# TestPCB2.net
KiCad netlist of a schematic drawn in Altium Designer
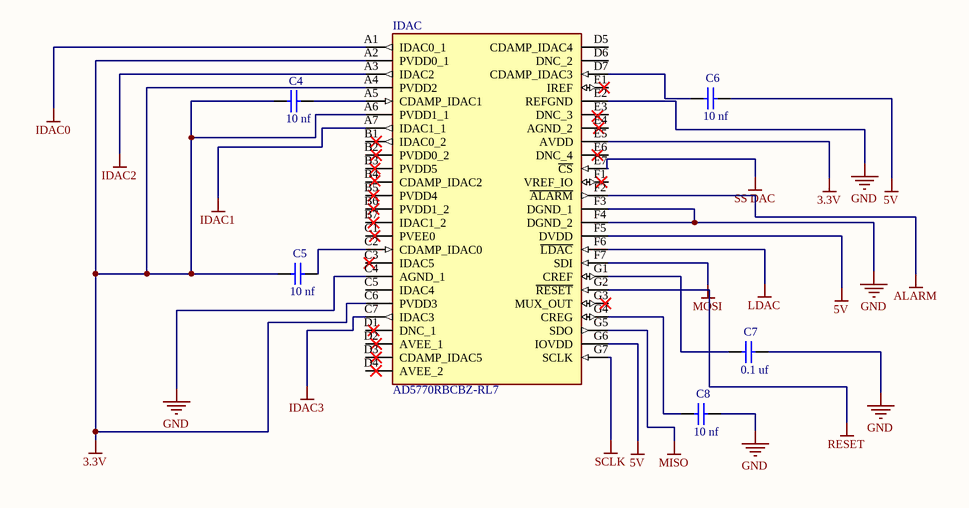
[diagram p0: TestPCB2.SchDoc]

(export (version "E")
  (design (tool "Eeschema 10.0.6"))
  (components
    (comp (ref "C4")
      (value "10 nf")
      (footprint "CAPC2013X94X50ML20T25")
      (fields
        (field (name "MANUFACTURER") "AVX Interconnect / Elco")
        (field (name "PART NUMBER") "08051C104JAT2A")
      )
      (libsource (lib "Altium Content Vault") (part "CAP"))
    )
    (comp (ref "C5")
      (value "10 nf")
      (footprint "CAPC2013X94X50ML20T25")
      (fields
        (field (name "MANUFACTURER") "AVX Interconnect / Elco")
        (field (name "PART NUMBER") "08051C104JAT2A")
      )
      (libsource (lib "Altium Content Vault") (part "CAP"))
    )
    (comp (ref "C6")
      (value "10 nf")
      (footprint "CAPC2013X94X50ML20T25")
      (fields
        (field (name "MANUFACTURER") "AVX Interconnect / Elco")
        (field (name "PART NUMBER") "08051C104JAT2A")
      )
      (libsource (lib "Altium Content Vault") (part "CAP"))
    )
    (comp (ref "C7")
      (value "0.1 uf")
      (footprint "CAPC2013X94X50ML20T25")
      (fields
        (field (name "MANUFACTURER") "AVX Interconnect / Elco")
        (field (name "PART NUMBER") "08051C104JAT2A")
      )
      (libsource (lib "Altium Content Vault") (part "CAP"))
    )
    (comp (ref "C8")
      (value "10 nf")
      (footprint "CAPC2013X94X50ML20T25")
      (fields
        (field (name "MANUFACTURER") "AVX Interconnect / Elco")
        (field (name "PART NUMBER") "08051C104JAT2A")
      )
      (libsource (lib "Altium Content Vault") (part "CAP"))
    )
    (comp (ref "IDAC")
      (value "AD5770RBCBZ-RL7")
      (footprint "SamacSys:BGA49C50P7X7_404X404X66")
      (description "Integrated Circuit")
      (fields (field (name "MOUSER PART NUMBER") "584-AD5770RBCBZ-RL7"))
      (libsource (lib "*") (part "AD5770RBCBZ-RL7"))
    )
  )
  (nets
    (net (code "1") (name "3.3V") (class "Default")
      (node (ref "C4") (pin "1") (pinfunction "1_1") (pintype "passive"))
      (node (ref "C5") (pin "1") (pinfunction "1_1") (pintype "passive"))
      (node (ref "IDAC") (pin "A2") (pinfunction "PVDD0_1_A2") (pintype "power_in"))
      (node (ref "IDAC") (pin "A4") (pinfunction "PVDD2_A4") (pintype "power_in"))
      (node (ref "IDAC") (pin "A6") (pinfunction "PVDD1_1_A6") (pintype "power_in"))
      (node (ref "IDAC") (pin "C6") (pinfunction "PVDD3_C6") (pintype "power_in"))
      (node (ref "IDAC") (pin "E5") (pinfunction "AVDD_E5") (pintype "power_in"))
    )
    (net (code "2") (name "5V") (class "Default")
      (node (ref "C6") (pin "2") (pinfunction "2_2") (pintype "passive"))
      (node (ref "IDAC") (pin "F5") (pinfunction "DVDD_F5") (pintype "power_in"))
      (node (ref "IDAC") (pin "G6") (pinfunction "IOVDD_G6") (pintype "power_in"))
    )
    (net (code "3") (name "ALARM") (class "Default")
      (node (ref "IDAC") (pin "F2") (pinfunction "~{ALARM}_F2") (pintype "output"))
    )
    (net (code "4") (name "GND") (class "Default")
      (node (ref "C7") (pin "2") (pinfunction "2_2") (pintype "passive"))
      (node (ref "C8") (pin "2") (pinfunction "2_2") (pintype "passive"))
      (node (ref "IDAC") (pin "C4") (pinfunction "AGND_1_C4") (pintype "power_in"))
      (node (ref "IDAC") (pin "E2") (pinfunction "REFGND_E2") (pintype "power_in"))
      (node (ref "IDAC") (pin "F3") (pinfunction "DGND_1_F3") (pintype "power_in"))
      (node (ref "IDAC") (pin "F4") (pinfunction "DGND_2_F4") (pintype "power_in"))
    )
    (net (code "5") (name "IDAC0") (class "Default")
      (node (ref "IDAC") (pin "A1") (pinfunction "IDAC0_1_A1") (pintype "output"))
    )
    (net (code "6") (name "IDAC1") (class "Default")
      (node (ref "IDAC") (pin "A7") (pinfunction "IDAC1_1_A7") (pintype "output"))
    )
    (net (code "7") (name "IDAC2") (class "Default")
      (node (ref "IDAC") (pin "A3") (pinfunction "IDAC2_A3") (pintype "output"))
    )
    (net (code "8") (name "IDAC3") (class "Default")
      (node (ref "IDAC") (pin "C7") (pinfunction "IDAC3_C7") (pintype "output"))
    )
    (net (code "9") (name "LDAC") (class "Default")
      (node (ref "IDAC") (pin "F6") (pinfunction "~{LDAC}_F6") (pintype "input"))
    )
    (net (code "10") (name "MISO") (class "Default")
      (node (ref "IDAC") (pin "G5") (pinfunction "SDO_G5") (pintype "output"))
    )
    (net (code "11") (name "MOSI") (class "Default")
      (node (ref "IDAC") (pin "F7") (pinfunction "SDI_F7") (pintype "input"))
    )
    (net (code "12") (name "Net-(IDAC-CDAMP_IDAC0)") (class "Default")
      (node (ref "C5") (pin "2") (pinfunction "2_2") (pintype "passive"))
      (node (ref "IDAC") (pin "C2") (pinfunction "CDAMP_IDAC0_C2") (pintype "input"))
    )
    (net (code "13") (name "Net-(IDAC-CDAMP_IDAC1)") (class "Default")
      (node (ref "C4") (pin "2") (pinfunction "2_2") (pintype "passive"))
      (node (ref "IDAC") (pin "A5") (pinfunction "CDAMP_IDAC1_A5") (pintype "input"))
    )
    (net (code "14") (name "Net-(IDAC-CDAMP_IDAC3)") (class "Default")
      (node (ref "C6") (pin "1") (pinfunction "1_1") (pintype "passive"))
      (node (ref "IDAC") (pin "D7") (pinfunction "CDAMP_IDAC3_D7") (pintype "input"))
    )
    (net (code "15") (name "Net-(IDAC-CREF)") (class "Default")
      (node (ref "C7") (pin "1") (pinfunction "1_1") (pintype "passive"))
      (node (ref "IDAC") (pin "G1") (pinfunction "CREF_G1") (pintype "bidirectional"))
    )
    (net (code "16") (name "Net-(IDAC-CREG)") (class "Default")
      (node (ref "C8") (pin "1") (pinfunction "1_1") (pintype "passive"))
      (node (ref "IDAC") (pin "G4") (pinfunction "CREG_G4") (pintype "bidirectional"))
    )
    (net (code "17") (name "RESET") (class "Default")
      (node (ref "IDAC") (pin "G2") (pinfunction "~{RESET}_G2") (pintype "input"))
    )
    (net (code "18") (name "SCLK") (class "Default")
      (node (ref "IDAC") (pin "G7") (pinfunction "SCLK_G7") (pintype "input"))
    )
    (net (code "19") (name "SS DAC") (class "Default")
      (node (ref "IDAC") (pin "E7") (pinfunction "~{CS}_E7") (pintype "input"))
    )
    (net (code "20") (name "unconnected-(IDAC-AGND_2-PadE4)") (class "Default")
      (node (ref "IDAC") (pin "E4") (pinfunction "AGND_2_E4") (pintype "power_in"))
    )
    (net (code "21") (name "unconnected-(IDAC-AVEE_1-PadD2)") (class "Default")
      (node (ref "IDAC") (pin "D2") (pinfunction "AVEE_1_D2") (pintype "power_in"))
    )
    (net (code "22") (name "unconnected-(IDAC-AVEE_2-PadD4)") (class "Default")
      (node (ref "IDAC") (pin "D4") (pinfunction "AVEE_2_D4") (pintype "power_in"))
    )
    (net (code "23") (name "unconnected-(IDAC-CDAMP_IDAC2-PadB4)") (class "Default")
      (node (ref "IDAC") (pin "B4") (pinfunction "CDAMP_IDAC2_B4") (pintype "passive"))
    )
    (net (code "24") (name "unconnected-(IDAC-CDAMP_IDAC4-PadD5)") (class "Default")
      (node (ref "IDAC") (pin "D5") (pinfunction "CDAMP_IDAC4_D5") (pintype "passive"))
    )
    (net (code "25") (name "unconnected-(IDAC-CDAMP_IDAC5-PadD3)") (class "Default")
      (node (ref "IDAC") (pin "D3") (pinfunction "CDAMP_IDAC5_D3") (pintype "passive"))
    )
    (net (code "26") (name "unconnected-(IDAC-DNC_1-PadD1)") (class "Default")
      (node (ref "IDAC") (pin "D1") (pinfunction "DNC_1_D1") (pintype "passive"))
    )
    (net (code "27") (name "unconnected-(IDAC-DNC_2-PadD6)") (class "Default")
      (node (ref "IDAC") (pin "D6") (pinfunction "DNC_2_D6") (pintype "passive"))
    )
    (net (code "28") (name "unconnected-(IDAC-DNC_3-PadE3)") (class "Default")
      (node (ref "IDAC") (pin "E3") (pinfunction "DNC_3_E3") (pintype "passive"))
    )
    (net (code "29") (name "unconnected-(IDAC-DNC_4-PadE6)") (class "Default")
      (node (ref "IDAC") (pin "E6") (pinfunction "DNC_4_E6") (pintype "passive"))
    )
    (net (code "30") (name "unconnected-(IDAC-IDAC0_2-PadB1)") (class "Default")
      (node (ref "IDAC") (pin "B1") (pinfunction "IDAC0_2_B1") (pintype "output"))
    )
    (net (code "31") (name "unconnected-(IDAC-IDAC1_2-PadB7)") (class "Default")
      (node (ref "IDAC") (pin "B7") (pinfunction "IDAC1_2_B7") (pintype "passive"))
    )
    (net (code "32") (name "unconnected-(IDAC-IDAC4-PadC5)") (class "Default")
      (node (ref "IDAC") (pin "C5") (pinfunction "IDAC4_C5") (pintype "passive"))
    )
    (net (code "33") (name "unconnected-(IDAC-IDAC5-PadC3)") (class "Default")
      (node (ref "IDAC") (pin "C3") (pinfunction "IDAC5_C3") (pintype "passive"))
    )
    (net (code "34") (name "unconnected-(IDAC-IREF-PadE1)") (class "Default")
      (node (ref "IDAC") (pin "E1") (pinfunction "IREF_E1") (pintype "bidirectional"))
    )
    (net (code "35") (name "unconnected-(IDAC-MUX_OUT-PadG3)") (class "Default")
      (node (ref "IDAC") (pin "G3") (pinfunction "MUX_OUT_G3") (pintype "bidirectional"))
    )
    (net (code "36") (name "unconnected-(IDAC-PVDD0_2-PadB2)") (class "Default")
      (node (ref "IDAC") (pin "B2") (pinfunction "PVDD0_2_B2") (pintype "power_in"))
    )
    (net (code "37") (name "unconnected-(IDAC-PVDD1_2-PadB6)") (class "Default")
      (node (ref "IDAC") (pin "B6") (pinfunction "PVDD1_2_B6") (pintype "power_in"))
    )
    (net (code "38") (name "unconnected-(IDAC-PVDD4-PadB5)") (class "Default")
      (node (ref "IDAC") (pin "B5") (pinfunction "PVDD4_B5") (pintype "power_in"))
    )
    (net (code "39") (name "unconnected-(IDAC-PVDD5-PadB3)") (class "Default")
      (node (ref "IDAC") (pin "B3") (pinfunction "PVDD5_B3") (pintype "power_in"))
    )
    (net (code "40") (name "unconnected-(IDAC-PVEE0-PadC1)") (class "Default")
      (node (ref "IDAC") (pin "C1") (pinfunction "PVEE0_C1") (pintype "power_in"))
    )
    (net (code "41") (name "unconnected-(IDAC-VREF_IO-PadF1)") (class "Default")
      (node (ref "IDAC") (pin "F1") (pinfunction "VREF_IO_F1") (pintype "bidirectional"))
    )
  )
)
